# SparkFun_ESLOV_to_Qwiic_Bridge.net
KiCad netlist of a schematic drawn in EAGLE
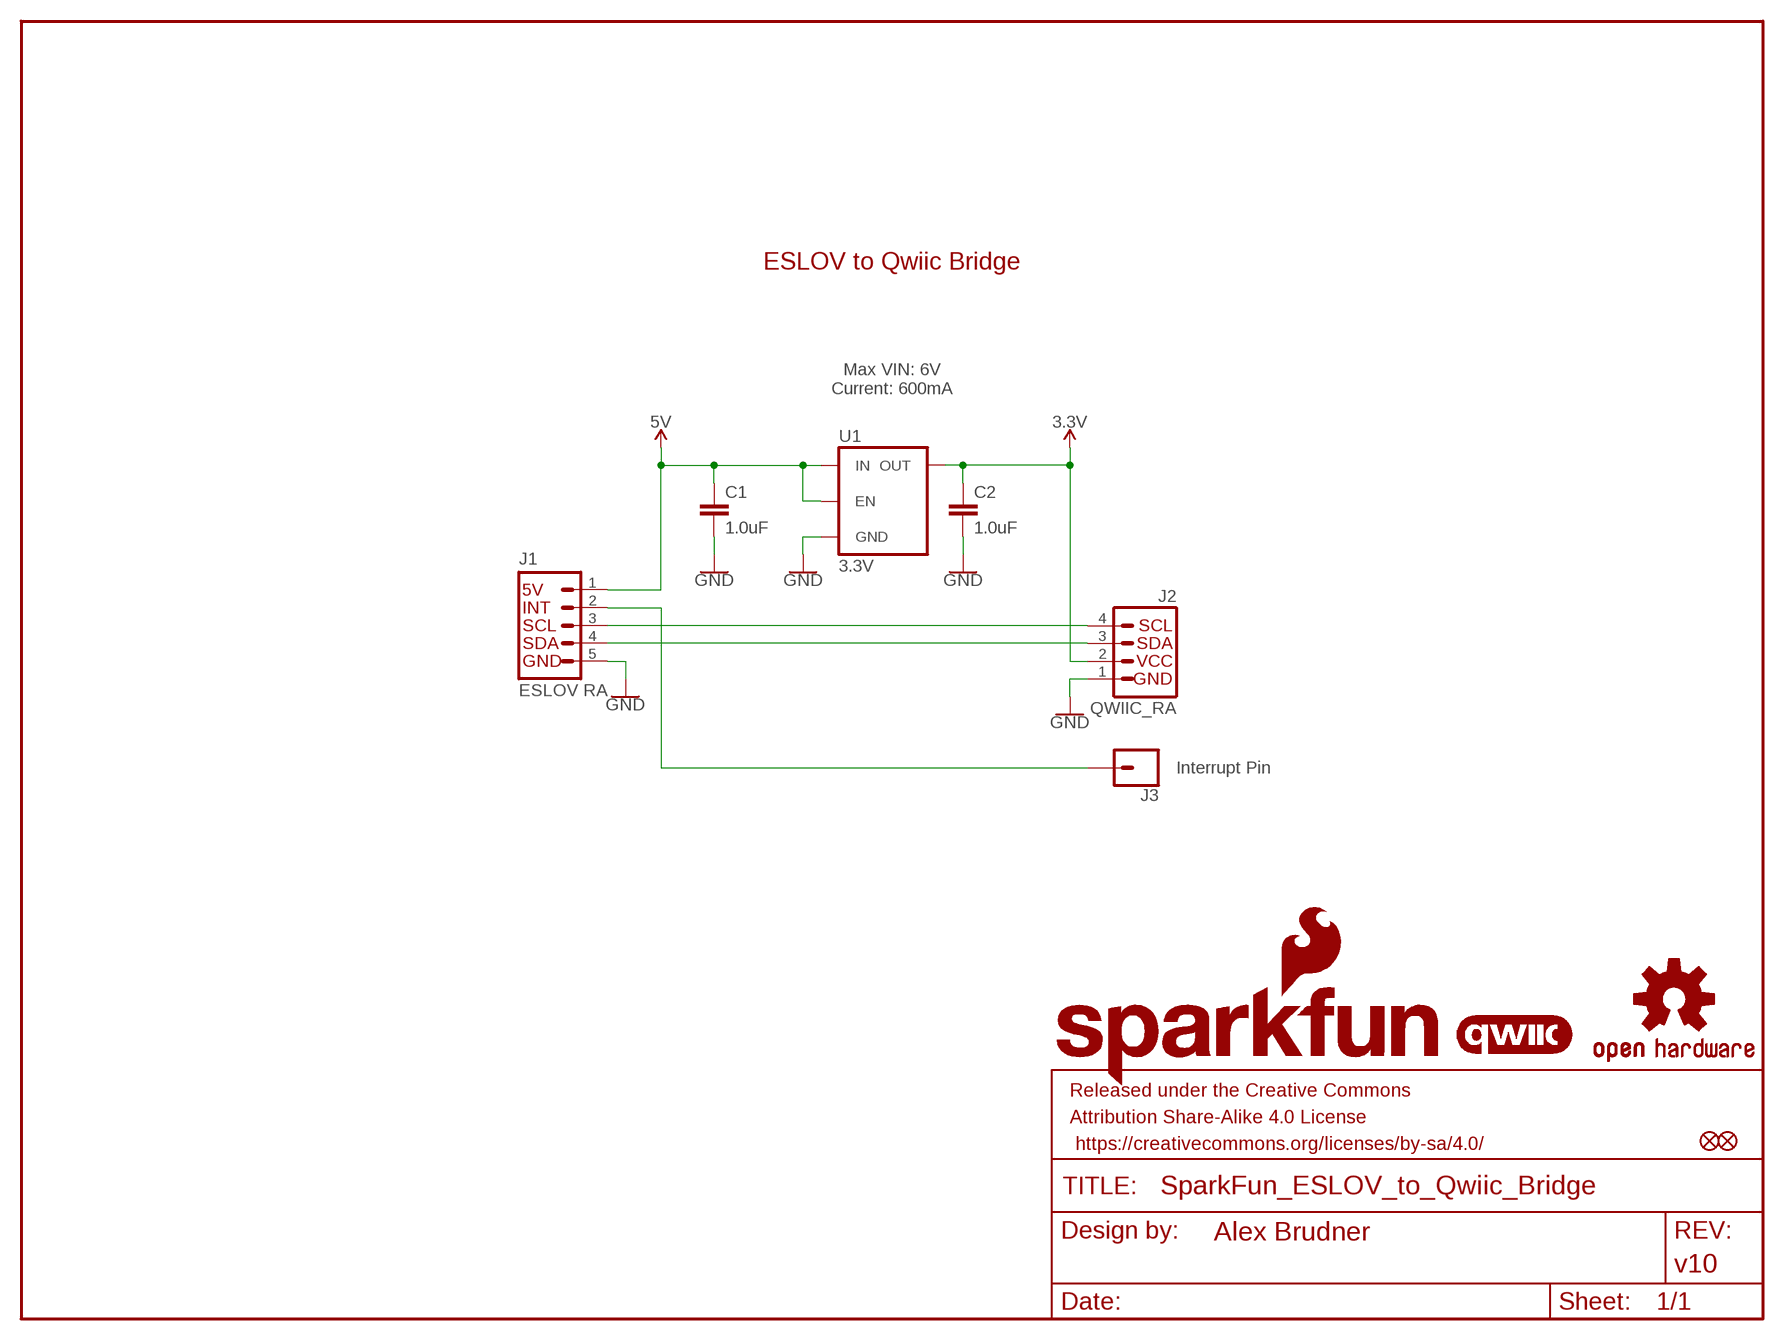
[diagram p0: schematic, sheet 1]

(export (version "E")
  (design (tool "Eeschema 10.0.6"))
  (components
    (comp (ref "C1")
      (value "1.0uF")
      (footprint "eagle-import:0402-TIGHT")
      (libsource (lib "eagle-import") (part "1.0UF-0402T-16V-10%"))
    )
    (comp (ref "C2")
      (value "1.0uF")
      (footprint "eagle-import:0402-TIGHT")
      (libsource (lib "eagle-import") (part "1.0UF-0402T-16V-10%"))
    )
    (comp (ref "FD1")
      (value "FIDUCIALUFIDUCIAL")
      (footprint "eagle-import:FIDUCIAL-MICRO")
      (libsource (lib "eagle-import") (part "FIDUCIALUFIDUCIAL"))
    )
    (comp (ref "FD2")
      (value "FIDUCIALUFIDUCIAL")
      (footprint "eagle-import:FIDUCIAL-MICRO")
      (libsource (lib "eagle-import") (part "FIDUCIALUFIDUCIAL"))
    )
    (comp (ref "FRAME1")
      (value "FRAME-LETTER")
      (footprint "eagle-import:CREATIVE_COMMONS")
      (fields (field (name "DESIGNER") "Alex Brudner") (field (name "REV") "v10"))
      (libsource (lib "eagle-import") (part "FRAME-LETTER"))
    )
    (comp (ref "J1")
      (value "ESLOV RA")
      (footprint "eagle-import:JST_5_1MM_RA")
      (libsource (lib "eagle-import") (part "ESLOV"))
    )
    (comp (ref "J2")
      (value "QWIIC_RA")
      (footprint "eagle-import:JST04_1MM_RA")
      (libsource (lib "eagle-import") (part "QWIIC_CONNECTORJS-1MM"))
    )
    (comp (ref "J3")
      (value "CONN_01")
      (footprint "eagle-import:1X01")
      (libsource (lib "eagle-import") (part "CONN_01"))
    )
    (comp (ref "LOGO1")
      (value "SFE_LOGO_NAME_FLAME.1_INCH")
      (footprint "eagle-import:SFE_LOGO_NAME_FLAME_.1")
      (libsource (lib "eagle-import") (part "SFE_LOGO_NAME_FLAME.1_INCH"))
    )
    (comp (ref "LOGO2")
      (value "OSHW-LOGOMINI")
      (footprint "eagle-import:OSHW-LOGO-MINI")
      (libsource (lib "eagle-import") (part "OSHW-LOGOMINI"))
    )
    (comp (ref "LOGO3")
      (value "QWIIC_LOGO_CONNECTOR")
      (footprint "eagle-import:QWIIC_5.5MM")
      (libsource (lib "eagle-import") (part "QWIIC_LOGO_CONNECTOR"))
    )
    (comp (ref "U1")
      (value "3.3V")
      (footprint "eagle-import:SOT23-5")
      (libsource (lib "eagle-import") (part "V_REG_AP2112K-3.3V"))
    )
  )
  (nets
    (net (code "1") (name "3.3V") (class "Default")
      (node (ref "C2") (pin "1") (pinfunction "1_1") (pintype "passive"))
      (node (ref "J2") (pin "2") (pinfunction "2_2") (pintype "power_in"))
      (node (ref "U1") (pin "5") (pinfunction "OUT_5") (pintype "passive"))
    )
    (net (code "2") (name "5V") (class "Default")
      (node (ref "C1") (pin "1") (pinfunction "1_1") (pintype "passive"))
      (node (ref "J1") (pin "1") (pinfunction "1_1") (pintype "power_in"))
      (node (ref "U1") (pin "1") (pinfunction "IN_1") (pintype "input"))
      (node (ref "U1") (pin "3") (pinfunction "EN_3") (pintype "input"))
    )
    (net (code "3") (name "GND") (class "Default")
      (node (ref "C1") (pin "2") (pinfunction "2_2") (pintype "passive"))
      (node (ref "C2") (pin "2") (pinfunction "2_2") (pintype "passive"))
      (node (ref "J1") (pin "5") (pinfunction "5_5") (pintype "power_in"))
      (node (ref "J2") (pin "1") (pinfunction "1_1") (pintype "power_in"))
      (node (ref "U1") (pin "2") (pinfunction "GND_2") (pintype "input"))
    )
    (net (code "4") (name "Net-(J1-Pad2)") (class "Default")
      (node (ref "J1") (pin "2") (pinfunction "2_2") (pintype "passive"))
      (node (ref "J3") (pin "1") (pinfunction "1_1") (pintype "passive"))
    )
    (net (code "5") (name "Net-(J1-Pad3)") (class "Default")
      (node (ref "J1") (pin "3") (pinfunction "3_3") (pintype "passive"))
      (node (ref "J2") (pin "4") (pinfunction "4_4") (pintype "passive"))
    )
    (net (code "6") (name "Net-(J1-Pad4)") (class "Default")
      (node (ref "J1") (pin "4") (pinfunction "4_4") (pintype "passive"))
      (node (ref "J2") (pin "3") (pinfunction "3_3") (pintype "passive"))
    )
  )
)
